# SCH_Rhian_s-Happy-Project_2024-12-22.net
KiCad netlist of a schematic drawn in EasyEDA
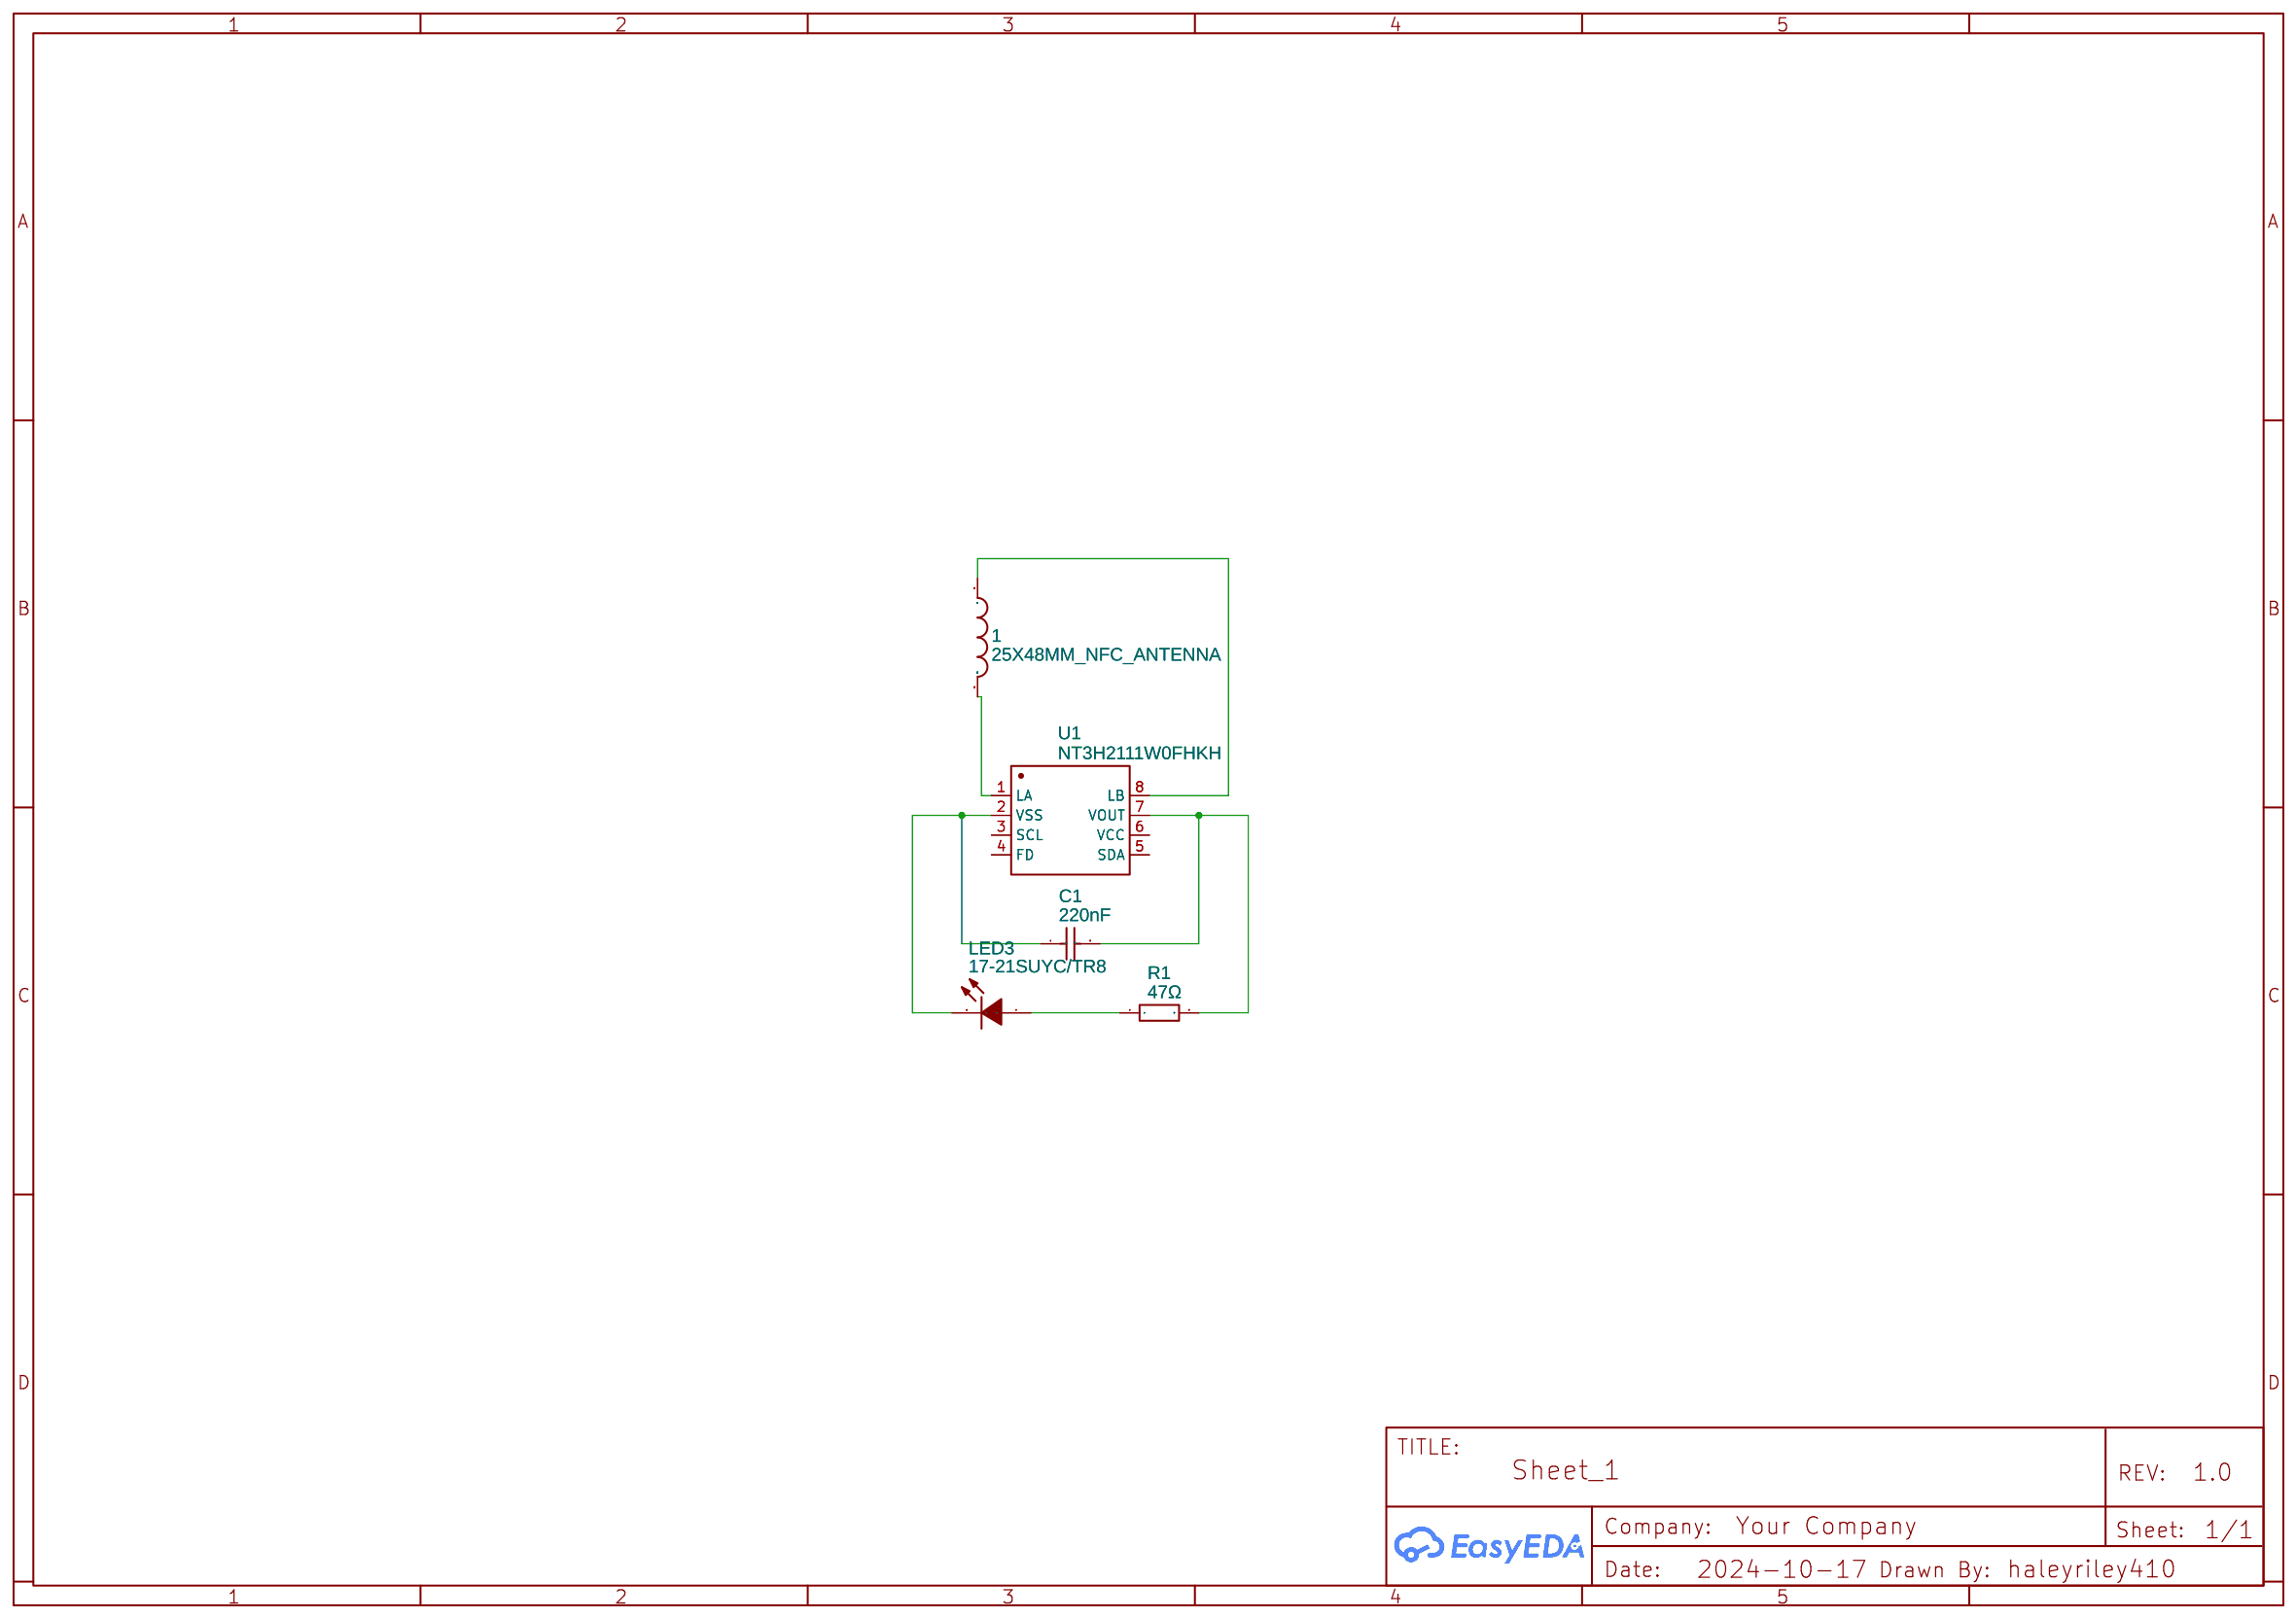
[diagram p0: schematic sheet]

(export (version "E")
  (design (tool "Eeschema 10.0.6"))
  (components
    (comp (ref "1") (value "25X48MM_NFC_ANTENNA") (libsource (lib "") (part "25X48MM_NFC_ANTENNA")))
    (comp (ref "C1")
      (value "220nF")
      (fields
        (field (name "Manufacturer Part") "CL10B224KA8NNNC")
        (field (name "Manufacturer") "SAMSUNG(三星)")
      )
      (libsource (lib "") (part "CL10B224KA8NNNC"))
    )
    (comp (ref "LED3")
      (value "17-21SUYC/TR8")
      (fields (field (name "Manufacturer Part") "KT-0805黄灯") (field (name "Manufacturer") "KENTO"))
      (libsource (lib "") (part "17-21SUYC/TR8"))
    )
    (comp (ref "R1")
      (value "47Ω")
      (fields
        (field (name "Manufacturer Part") "0603WAF470JT5E")
        (field (name "Manufacturer") "UNI-ROYAL(厚声)")
      )
      (libsource (lib "") (part "0603WAF470JT5E"))
    )
    (comp (ref "U1")
      (value "NT3H2111W0FHKH")
      (fields (field (name "Manufacturer") "NXP(恩智浦)"))
      (libsource (lib "") (part "NT3H2111W0FHKH"))
    )
  )
  (nets
    (net (code "1") (name "Net-(LED3-+)") (class "Default")
      (node (ref "LED3") (pin "1") (pinfunction "+_1") (pintype "unspecified"))
      (node (ref "R1") (pin "1") (pinfunction "1_1") (pintype "input"))
    )
    (net (code "2") (name "Net-(LED3--)") (class "Default")
      (node (ref "C1") (pin "1") (pinfunction "1_1") (pintype "input"))
      (node (ref "LED3") (pin "2") (pinfunction "-_2") (pintype "unspecified"))
      (node (ref "U1") (pin "2") (pinfunction "VSS_2") (pintype "unspecified"))
    )
    (net (code "3") (name "Net-(U1-LA)") (class "Default")
      (node (ref "1") (pin "P$2") (pinfunction "P$2_P$2") (pintype "bidirectional"))
      (node (ref "U1") (pin "1") (pinfunction "LA_1") (pintype "unspecified"))
    )
    (net (code "4") (name "Net-(U1-LB)") (class "Default")
      (node (ref "1") (pin "P$1") (pinfunction "P$1_P$1") (pintype "bidirectional"))
      (node (ref "U1") (pin "8") (pinfunction "LB_8") (pintype "unspecified"))
    )
    (net (code "5") (name "Net-(U1-VOUT)") (class "Default")
      (node (ref "C1") (pin "2") (pinfunction "2_2") (pintype "input"))
      (node (ref "R1") (pin "2") (pinfunction "2_2") (pintype "input"))
      (node (ref "U1") (pin "7") (pinfunction "VOUT_7") (pintype "unspecified"))
    )
    (net (code "6") (name "unconnected-(U1-FD-Pad4)") (class "Default")
      (node (ref "U1") (pin "4") (pinfunction "FD_4") (pintype "unspecified"))
    )
    (net (code "7") (name "unconnected-(U1-SCL-Pad3)") (class "Default")
      (node (ref "U1") (pin "3") (pinfunction "SCL_3") (pintype "unspecified"))
    )
    (net (code "8") (name "unconnected-(U1-SDA-Pad5)") (class "Default")
      (node (ref "U1") (pin "5") (pinfunction "SDA_5") (pintype "unspecified"))
    )
    (net (code "9") (name "unconnected-(U1-VCC-Pad6)") (class "Default")
      (node (ref "U1") (pin "6") (pinfunction "VCC_6") (pintype "unspecified"))
    )
  )
)
